# irrigation_shield.net
KiCad netlist of a schematic drawn in EAGLE
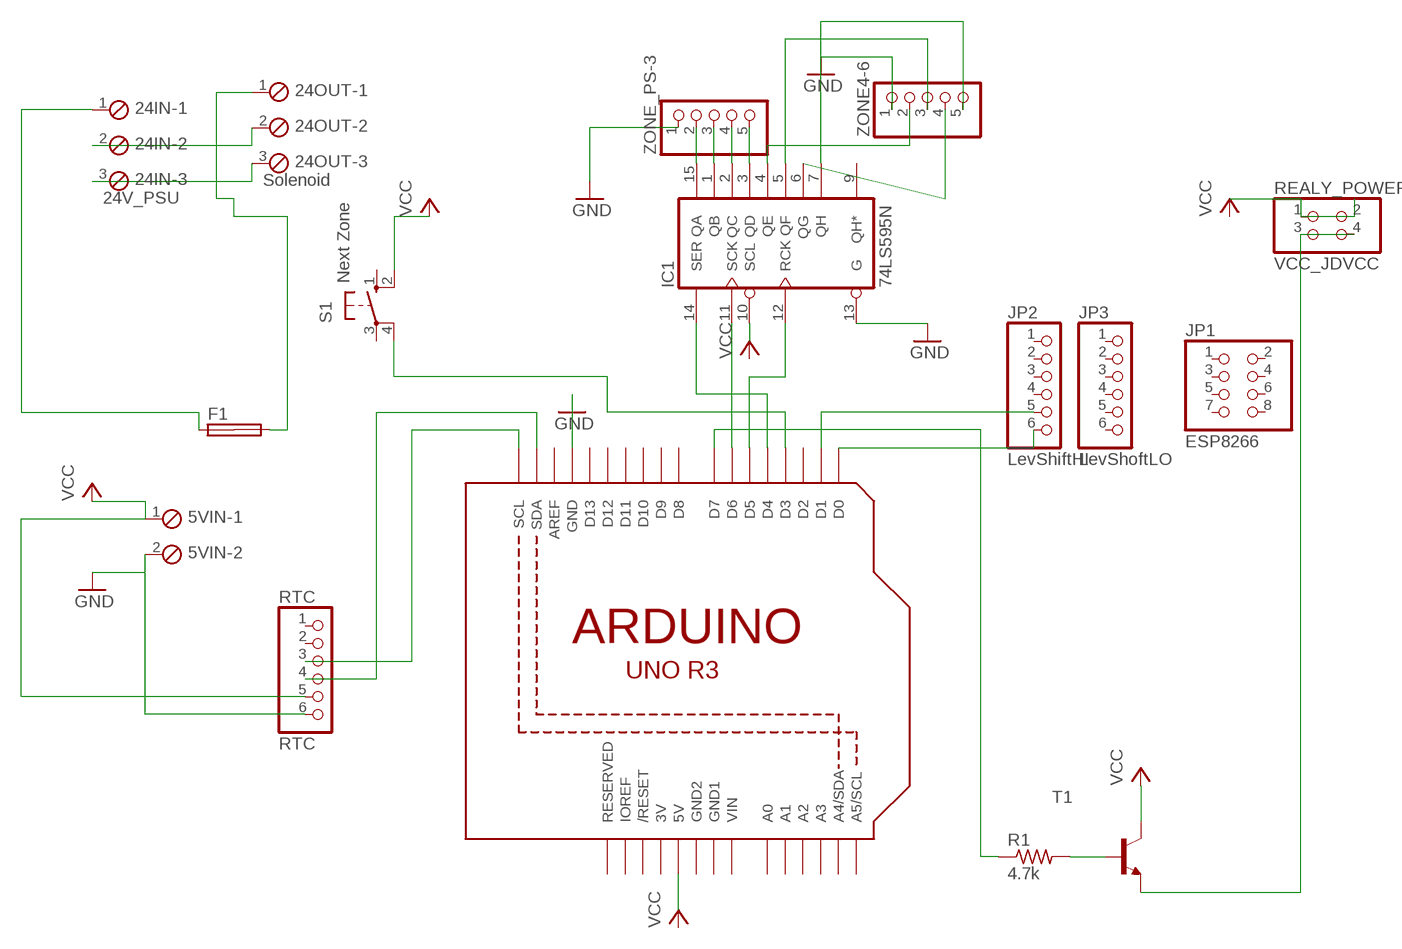
[diagram p0: schematic, sheet 1]

(export (version "E")
  (design (tool "Eeschema 10.0.6"))
  (components
    (comp (ref "5VIN")
      (value "MPT2")
      (footprint "eagle-import:2POL254")
      (libsource (lib "eagle-import") (part "MPT2"))
    )
    (comp (ref "24IN")
      (value "24V_PSU")
      (footprint "eagle-import:3POL254")
      (libsource (lib "eagle-import") (part "MPT3"))
    )
    (comp (ref "24OUT")
      (value "Solenoid")
      (footprint "eagle-import:3POL254")
      (libsource (lib "eagle-import") (part "MPT3"))
    )
    (comp (ref "F1")
      (value "SH32")
      (footprint "eagle-import:SH35")
      (libsource (lib "eagle-import") (part "SH32"))
    )
    (comp (ref "IC1")
      (value "74LS595N")
      (footprint "eagle-import:DIL16")
      (libsource (lib "eagle-import") (part "74595NLS"))
    )
    (comp (ref "JP1")
      (value "ESP8266")
      (footprint "eagle-import:2X04")
      (libsource (lib "eagle-import") (part "PINHD-2X4"))
    )
    (comp (ref "JP2")
      (value "LevShiftHI")
      (footprint "eagle-import:1X06")
      (libsource (lib "eagle-import") (part "PINHD-1X6"))
    )
    (comp (ref "JP3")
      (value "LevShoftLO")
      (footprint "eagle-import:1X06")
      (libsource (lib "eagle-import") (part "PINHD-1X6"))
    )
    (comp (ref "R1")
      (value "4.7k")
      (footprint "eagle-import:0207_7")
      (libsource (lib "eagle-import") (part "R-US_0207/7"))
    )
    (comp (ref "REALY_POWER")
      (value "VCC_JDVCC")
      (footprint "eagle-import:2X02")
      (libsource (lib "eagle-import") (part "PINHD-2X2"))
    )
    (comp (ref "RTC")
      (value "RTC")
      (footprint "eagle-import:1X06_90")
      (libsource (lib "eagle-import") (part "PINHD-1X6/90"))
    )
    (comp (ref "S1")
      (value "Next Zone")
      (footprint "eagle-import:B3F-10XX")
      (fields (field (name "MPN") "B3F-1000"))
      (libsource (lib "eagle-import") (part "10-XX"))
    )
    (comp (ref "T1")
      (value "-NPN-TO92")
      (footprint "eagle-import:TO92")
      (libsource (lib "eagle-import") (part "-NPN-TO92"))
    )
    (comp (ref "U1")
      (value "ARDUINOR3-DIMENSION")
      (footprint "eagle-import:ARDUINOR3")
      (libsource (lib "eagle-import") (part "ARDUINOR3-DIMENSION"))
    )
    (comp (ref "ZONE4-6")
      (value "PINHD-1X5")
      (footprint "eagle-import:1X05")
      (libsource (lib "eagle-import") (part "PINHD-1X5"))
    )
    (comp (ref "ZONE_PS-3")
      (value "PINHD-1X5")
      (footprint "eagle-import:1X05")
      (libsource (lib "eagle-import") (part "PINHD-1X5"))
    )
  )
  (nets
    (net (code "1") (name "/3V") (class "Default")
      (node (ref "U1") (pin "3V") (pinfunction "3V_3V") (pintype "power_in"))
    )
    (net (code "2") (name "/GND1") (class "Default")
      (node (ref "U1") (pin "GND1") (pinfunction "GND1_GND1") (pintype "power_in"))
    )
    (net (code "3") (name "/GND2") (class "Default")
      (node (ref "U1") (pin "GND2") (pinfunction "GND2_GND2") (pintype "power_in"))
    )
    (net (code "4") (name "/VIN") (class "Default")
      (node (ref "U1") (pin "VIN") (pinfunction "VIN_VIN") (pintype "power_in"))
    )
    (net (code "5") (name "GND") (class "Default")
      (node (ref "5VIN") (pin "2") (pinfunction "1_2") (pintype "passive"))
      (node (ref "IC1") (pin "13") (pinfunction "G_13") (pintype "input"))
      (node (ref "RTC") (pin "6") (pinfunction "6_6") (pintype "passive"))
      (node (ref "U1") (pin "GND") (pinfunction "GND_GND") (pintype "power_in"))
      (node (ref "ZONE4-6") (pin "1") (pinfunction "1_1") (pintype "passive"))
      (node (ref "ZONE_PS-3") (pin "1") (pinfunction "1_1") (pintype "passive"))
    )
    (net (code "6") (name "Net-(24IN-Pad1)") (class "Default")
      (node (ref "24IN") (pin "1") (pinfunction "1_1") (pintype "passive"))
      (node (ref "F1") (pin "1A") (pinfunction "1A_1A") (pintype "passive"))
    )
    (net (code "7") (name "Net-(24INB-1)") (class "Default")
      (node (ref "24IN") (pin "2") (pinfunction "1_2") (pintype "passive"))
      (node (ref "24OUT") (pin "2") (pinfunction "1_2") (pintype "passive"))
    )
    (net (code "8") (name "Net-(24INC-1)") (class "Default")
      (node (ref "24IN") (pin "3") (pinfunction "1_3") (pintype "passive"))
      (node (ref "24OUT") (pin "3") (pinfunction "1_3") (pintype "passive"))
    )
    (net (code "9") (name "Net-(24OUT-Pad1)") (class "Default")
      (node (ref "24OUT") (pin "1") (pinfunction "1_1") (pintype "passive"))
      (node (ref "F1") (pin "2A") (pinfunction "2A_2A") (pintype "passive"))
    )
    (net (code "10") (name "Net-(IC1A-QA)") (class "Default")
      (node (ref "IC1") (pin "15") (pinfunction "QA_15") (pintype "tri_state"))
      (node (ref "ZONE_PS-3") (pin "2") (pinfunction "2_2") (pintype "passive"))
    )
    (net (code "11") (name "Net-(IC1A-QB)") (class "Default")
      (node (ref "IC1") (pin "1") (pinfunction "QB_1") (pintype "tri_state"))
      (node (ref "ZONE_PS-3") (pin "3") (pinfunction "3_3") (pintype "passive"))
    )
    (net (code "12") (name "Net-(IC1A-QC)") (class "Default")
      (node (ref "IC1") (pin "2") (pinfunction "QC_2") (pintype "tri_state"))
      (node (ref "ZONE_PS-3") (pin "4") (pinfunction "4_4") (pintype "passive"))
    )
    (net (code "13") (name "Net-(IC1A-QD)") (class "Default")
      (node (ref "IC1") (pin "3") (pinfunction "QD_3") (pintype "tri_state"))
      (node (ref "ZONE_PS-3") (pin "5") (pinfunction "5_5") (pintype "passive"))
    )
    (net (code "14") (name "Net-(IC1A-QE)") (class "Default")
      (node (ref "IC1") (pin "4") (pinfunction "QE_4") (pintype "tri_state"))
      (node (ref "ZONE4-6") (pin "2") (pinfunction "2_2") (pintype "passive"))
    )
    (net (code "15") (name "Net-(IC1A-QF)") (class "Default")
      (node (ref "IC1") (pin "5") (pinfunction "QF_5") (pintype "tri_state"))
      (node (ref "ZONE4-6") (pin "3") (pinfunction "3_3") (pintype "passive"))
    )
    (net (code "16") (name "Net-(IC1A-QG)") (class "Default")
      (node (ref "IC1") (pin "6") (pinfunction "QG_6") (pintype "tri_state"))
      (node (ref "ZONE4-6") (pin "4") (pinfunction "4_4") (pintype "passive"))
    )
    (net (code "17") (name "Net-(IC1A-QH)") (class "Default")
      (node (ref "IC1") (pin "7") (pinfunction "QH_7") (pintype "tri_state"))
      (node (ref "ZONE4-6") (pin "5") (pinfunction "5_5") (pintype "passive"))
    )
    (net (code "18") (name "Net-(IC1A-RCK)") (class "Default")
      (node (ref "IC1") (pin "12") (pinfunction "RCK_12") (pintype "input"))
      (node (ref "U1") (pin "D5") (pinfunction "D5_D5") (pintype "bidirectional"))
    )
    (net (code "19") (name "Net-(IC1A-SCK)") (class "Default")
      (node (ref "IC1") (pin "11") (pinfunction "SCK_11") (pintype "input"))
      (node (ref "U1") (pin "D6") (pinfunction "D6_D6") (pintype "bidirectional"))
    )
    (net (code "20") (name "Net-(IC1A-SER)") (class "Default")
      (node (ref "IC1") (pin "14") (pinfunction "SER_14") (pintype "input"))
      (node (ref "U1") (pin "D4") (pinfunction "D4_D4") (pintype "bidirectional"))
    )
    (net (code "21") (name "Net-(JP2-Pad5)") (class "Default")
      (node (ref "JP2") (pin "5") (pinfunction "5_5") (pintype "passive"))
      (node (ref "U1") (pin "D1") (pinfunction "D1_D1") (pintype "bidirectional"))
    )
    (net (code "22") (name "Net-(JP2-Pad6)") (class "Default")
      (node (ref "JP2") (pin "6") (pinfunction "6_6") (pintype "passive"))
      (node (ref "U1") (pin "D0") (pinfunction "D0_D0") (pintype "bidirectional"))
    )
    (net (code "23") (name "Net-(R1-Pad1)") (class "Default")
      (node (ref "R1") (pin "1") (pinfunction "1_1") (pintype "passive"))
      (node (ref "U1") (pin "D7") (pinfunction "D7_D7") (pintype "bidirectional"))
    )
    (net (code "24") (name "Net-(REALY_POWER-Pad1)") (class "Default")
      (node (ref "REALY_POWER") (pin "1") (pinfunction "1_1") (pintype "passive"))
      (node (ref "REALY_POWER") (pin "2") (pinfunction "2_2") (pintype "passive"))
    )
    (net (code "25") (name "Net-(RTC-Pad3)") (class "Default")
      (node (ref "RTC") (pin "3") (pinfunction "3_3") (pintype "passive"))
      (node (ref "U1") (pin "SCL") (pinfunction "SCL_SCL") (pintype "bidirectional"))
    )
    (net (code "26") (name "Net-(RTC-Pad4)") (class "Default")
      (node (ref "RTC") (pin "4") (pinfunction "4_4") (pintype "passive"))
      (node (ref "U1") (pin "SDA") (pinfunction "SDA_SDA") (pintype "bidirectional"))
    )
    (net (code "27") (name "Net-(S1-P1)") (class "Default")
      (node (ref "S1") (pin "4") (pinfunction "P1_4") (pintype "passive"))
      (node (ref "U1") (pin "D3") (pinfunction "D3_D3") (pintype "bidirectional"))
    )
    (net (code "28") (name "Net-(T1-B)") (class "Default")
      (node (ref "R1") (pin "2") (pinfunction "2_2") (pintype "passive"))
      (node (ref "T1") (pin "2") (pinfunction "B_2") (pintype "passive"))
    )
    (net (code "29") (name "Net-(T1-E)") (class "Default")
      (node (ref "REALY_POWER") (pin "3") (pinfunction "3_3") (pintype "passive"))
      (node (ref "REALY_POWER") (pin "4") (pinfunction "4_4") (pintype "passive"))
      (node (ref "T1") (pin "1") (pinfunction "E_1") (pintype "passive"))
    )
    (net (code "30") (name "VCC") (class "Default")
      (node (ref "5VIN") (pin "1") (pinfunction "1_1") (pintype "passive"))
      (node (ref "IC1") (pin "10") (pinfunction "SCL_10") (pintype "input"))
      (node (ref "RTC") (pin "5") (pinfunction "5_5") (pintype "passive"))
      (node (ref "S1") (pin "2") (pinfunction "S1_2") (pintype "passive"))
      (node (ref "T1") (pin "3") (pinfunction "C_3") (pintype "passive"))
      (node (ref "U1") (pin "5V") (pinfunction "5V_5V") (pintype "power_in"))
    )
    (net (code "31") (name "unconnected-(F1-Pad1B)") (class "Default")
      (node (ref "F1") (pin "1B") (pinfunction "1B_1B") (pintype "passive"))
    )
    (net (code "32") (name "unconnected-(F1-Pad2B)") (class "Default")
      (node (ref "F1") (pin "2B") (pinfunction "2B_2B") (pintype "passive"))
    )
    (net (code "33") (name "unconnected-(IC1A-QH*-Pad9)") (class "Default")
      (node (ref "IC1") (pin "9") (pinfunction "QH*_9") (pintype "tri_state"))
    )
    (net (code "34") (name "unconnected-(JP1-Pad1)") (class "Default")
      (node (ref "JP1") (pin "1") (pinfunction "1_1") (pintype "passive"))
    )
    (net (code "35") (name "unconnected-(JP1-Pad2)") (class "Default")
      (node (ref "JP1") (pin "2") (pinfunction "2_2") (pintype "passive"))
    )
    (net (code "36") (name "unconnected-(JP1-Pad3)") (class "Default")
      (node (ref "JP1") (pin "3") (pinfunction "3_3") (pintype "passive"))
    )
    (net (code "37") (name "unconnected-(JP1-Pad4)") (class "Default")
      (node (ref "JP1") (pin "4") (pinfunction "4_4") (pintype "passive"))
    )
    (net (code "38") (name "unconnected-(JP1-Pad5)") (class "Default")
      (node (ref "JP1") (pin "5") (pinfunction "5_5") (pintype "passive"))
    )
    (net (code "39") (name "unconnected-(JP1-Pad6)") (class "Default")
      (node (ref "JP1") (pin "6") (pinfunction "6_6") (pintype "passive"))
    )
    (net (code "40") (name "unconnected-(JP1-Pad7)") (class "Default")
      (node (ref "JP1") (pin "7") (pinfunction "7_7") (pintype "passive"))
    )
    (net (code "41") (name "unconnected-(JP1-Pad8)") (class "Default")
      (node (ref "JP1") (pin "8") (pinfunction "8_8") (pintype "passive"))
    )
    (net (code "42") (name "unconnected-(JP2-Pad1)") (class "Default")
      (node (ref "JP2") (pin "1") (pinfunction "1_1") (pintype "passive"))
    )
    (net (code "43") (name "unconnected-(JP2-Pad2)") (class "Default")
      (node (ref "JP2") (pin "2") (pinfunction "2_2") (pintype "passive"))
    )
    (net (code "44") (name "unconnected-(JP2-Pad3)") (class "Default")
      (node (ref "JP2") (pin "3") (pinfunction "3_3") (pintype "passive"))
    )
    (net (code "45") (name "unconnected-(JP2-Pad4)") (class "Default")
      (node (ref "JP2") (pin "4") (pinfunction "4_4") (pintype "passive"))
    )
    (net (code "46") (name "unconnected-(JP3-Pad1)") (class "Default")
      (node (ref "JP3") (pin "1") (pinfunction "1_1") (pintype "passive"))
    )
    (net (code "47") (name "unconnected-(JP3-Pad2)") (class "Default")
      (node (ref "JP3") (pin "2") (pinfunction "2_2") (pintype "passive"))
    )
    (net (code "48") (name "unconnected-(JP3-Pad3)") (class "Default")
      (node (ref "JP3") (pin "3") (pinfunction "3_3") (pintype "passive"))
    )
    (net (code "49") (name "unconnected-(JP3-Pad4)") (class "Default")
      (node (ref "JP3") (pin "4") (pinfunction "4_4") (pintype "passive"))
    )
    (net (code "50") (name "unconnected-(JP3-Pad5)") (class "Default")
      (node (ref "JP3") (pin "5") (pinfunction "5_5") (pintype "passive"))
    )
    (net (code "51") (name "unconnected-(JP3-Pad6)") (class "Default")
      (node (ref "JP3") (pin "6") (pinfunction "6_6") (pintype "passive"))
    )
    (net (code "52") (name "unconnected-(RTC-Pad1)") (class "Default")
      (node (ref "RTC") (pin "1") (pinfunction "1_1") (pintype "passive"))
    )
    (net (code "53") (name "unconnected-(RTC-Pad2)") (class "Default")
      (node (ref "RTC") (pin "2") (pinfunction "2_2") (pintype "passive"))
    )
    (net (code "54") (name "unconnected-(S1-P-Pad3)") (class "Default")
      (node (ref "S1") (pin "3") (pinfunction "P_3") (pintype "passive"))
    )
    (net (code "55") (name "unconnected-(S1-S-Pad1)") (class "Default")
      (node (ref "S1") (pin "1") (pinfunction "S_1") (pintype "passive"))
    )
    (net (code "56") (name "unconnected-(U1-A4{slash}SDA-PadA4)") (class "Default")
      (node (ref "U1") (pin "A4") (pinfunction "A4/SDA_A4") (pintype "bidirectional"))
    )
    (net (code "57") (name "unconnected-(U1-A5{slash}SCL-PadA5)") (class "Default")
      (node (ref "U1") (pin "A5") (pinfunction "A5/SCL_A5") (pintype "bidirectional"))
    )
    (net (code "58") (name "unconnected-(U1-PadA0)") (class "Default")
      (node (ref "U1") (pin "A0") (pinfunction "A0_A0") (pintype "bidirectional"))
    )
    (net (code "59") (name "unconnected-(U1-PadA1)") (class "Default")
      (node (ref "U1") (pin "A1") (pinfunction "A1_A1") (pintype "bidirectional"))
    )
    (net (code "60") (name "unconnected-(U1-PadA2)") (class "Default")
      (node (ref "U1") (pin "A2") (pinfunction "A2_A2") (pintype "bidirectional"))
    )
    (net (code "61") (name "unconnected-(U1-PadA3)") (class "Default")
      (node (ref "U1") (pin "A3") (pinfunction "A3_A3") (pintype "bidirectional"))
    )
    (net (code "62") (name "unconnected-(U1-PadAREF)") (class "Default")
      (node (ref "U1") (pin "AREF") (pinfunction "AREF_AREF") (pintype "bidirectional"))
    )
    (net (code "63") (name "unconnected-(U1-PadD2)") (class "Default")
      (node (ref "U1") (pin "D2") (pinfunction "D2_D2") (pintype "bidirectional"))
    )
    (net (code "64") (name "unconnected-(U1-PadD8)") (class "Default")
      (node (ref "U1") (pin "D8") (pinfunction "D8_D8") (pintype "bidirectional"))
    )
    (net (code "65") (name "unconnected-(U1-PadD9)") (class "Default")
      (node (ref "U1") (pin "D9") (pinfunction "D9_D9") (pintype "bidirectional"))
    )
    (net (code "66") (name "unconnected-(U1-PadD10)") (class "Default")
      (node (ref "U1") (pin "D10") (pinfunction "D10_D10") (pintype "bidirectional"))
    )
    (net (code "67") (name "unconnected-(U1-PadD11)") (class "Default")
      (node (ref "U1") (pin "D11") (pinfunction "D11_D11") (pintype "bidirectional"))
    )
    (net (code "68") (name "unconnected-(U1-PadD12)") (class "Default")
      (node (ref "U1") (pin "D12") (pinfunction "D12_D12") (pintype "bidirectional"))
    )
    (net (code "69") (name "unconnected-(U1-PadD13)") (class "Default")
      (node (ref "U1") (pin "D13") (pinfunction "D13_D13") (pintype "bidirectional"))
    )
    (net (code "70") (name "unconnected-(U1-PadIOREF)") (class "Default")
      (node (ref "U1") (pin "IOREF") (pinfunction "IOREF_IOREF") (pintype "output"))
    )
    (net (code "71") (name "unconnected-(U1-PadRESERVED)") (class "Default")
      (node (ref "U1") (pin "RESERVED") (pinfunction "RESERVED_RESERVED") (pintype "no_connect"))
    )
    (net (code "72") (name "unconnected-(U1-{slash}RESET-PadRESET)") (class "Default")
      (node (ref "U1") (pin "RESET") (pinfunction "/RESET_RESET") (pintype "bidirectional"))
    )
  )
)
